# Amplifier.net
KiCad netlist of a schematic drawn in Altium Designer
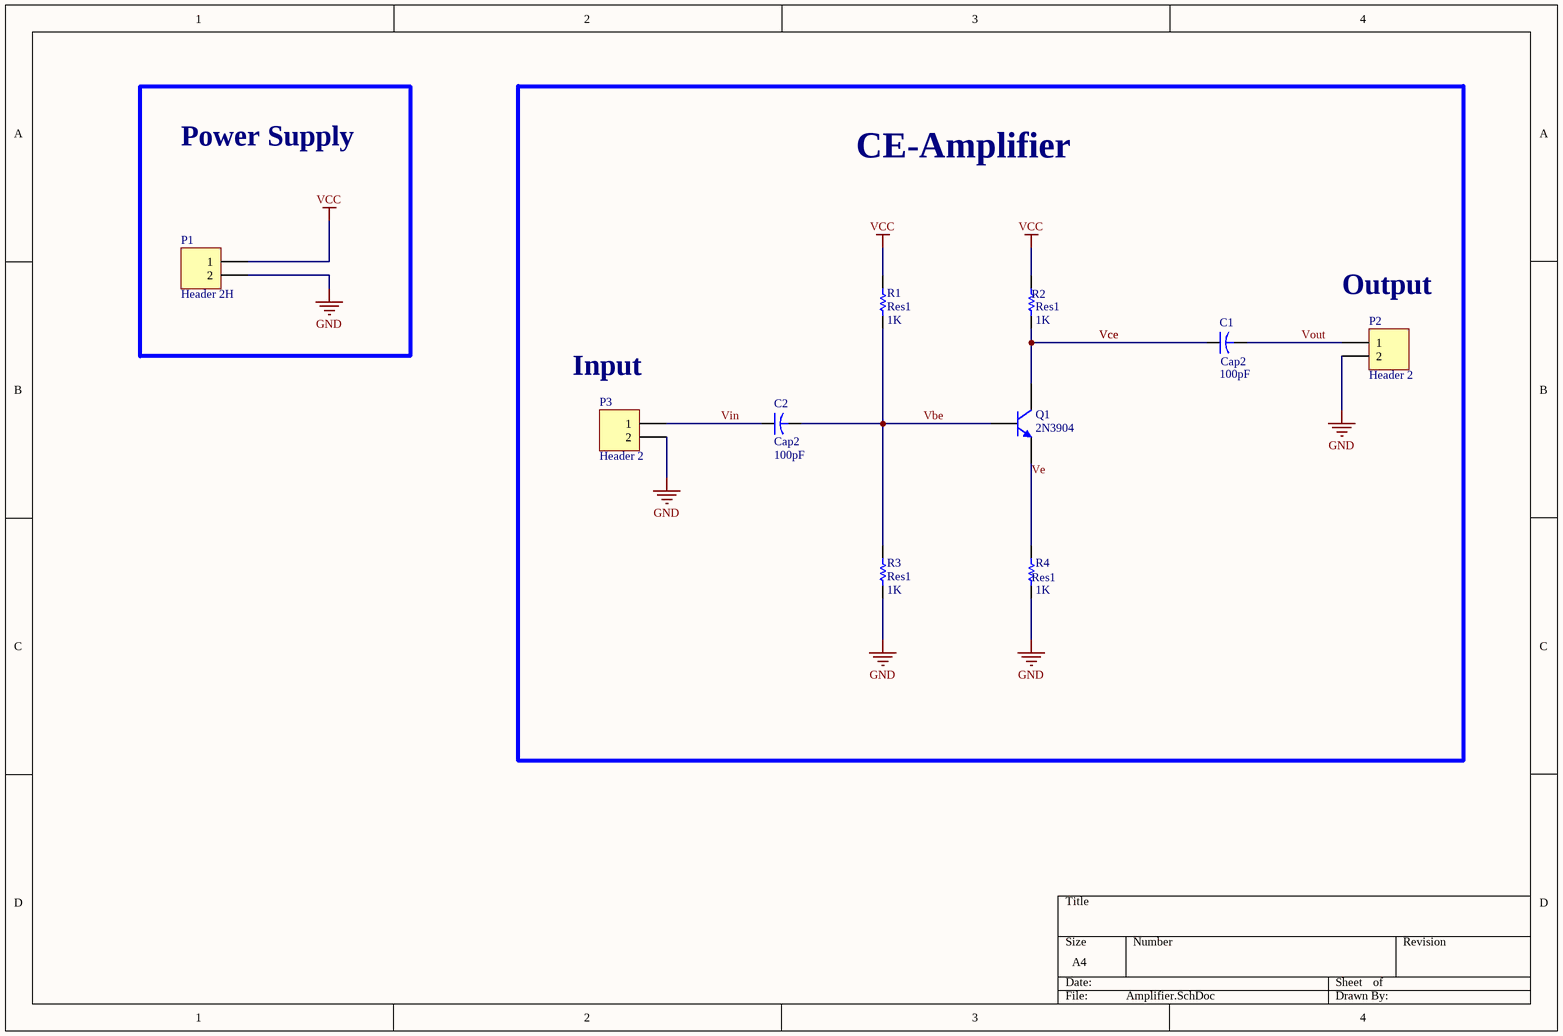
[diagram p0: Amplifier.SchDoc]

(export (version "E")
  (design (tool "Eeschema 10.0.6"))
  (components
    (comp (ref "C1")
      (value "Cap2")
      (footprint "CAPR5-4X5")
      (description "Capacitor")
      (fields (field (name "ALTIUM_VALUE") "100pF") (field (name "PUBLISHER") "Altium Limited"))
      (libsource (lib "Miscellaneous Devices") (part "Cap2"))
    )
    (comp (ref "C2")
      (value "Cap2")
      (footprint "CAPR5-4X5")
      (description "Capacitor")
      (fields (field (name "ALTIUM_VALUE") "100pF") (field (name "PUBLISHER") "Altium Limited"))
      (libsource (lib "Miscellaneous Devices") (part "Cap2"))
    )
    (comp (ref "P1")
      (value "Header 2H")
      (footprint "HDR1X2H")
      (description "Header, 2-Pin, Right Angle")
      (fields (field (name "PUBLISHER") "Altium Limited"))
      (libsource (lib "Miscellaneous Connectors") (part "Header 2H"))
    )
    (comp (ref "P2")
      (value "Header 2")
      (footprint "HDR1X2")
      (description "Header, 2-Pin")
      (fields (field (name "PUBLISHER") "Altium Limited"))
      (libsource (lib "Miscellaneous Connectors") (part "Header 2"))
    )
    (comp (ref "P3")
      (value "Header 2")
      (footprint "HDR1X2")
      (description "Header, 2-Pin")
      (fields (field (name "PUBLISHER") "Altium Limited"))
      (libsource (lib "") (part "Header 2_1"))
    )
    (comp (ref "Q1")
      (value "2N3904")
      (footprint "TO-92A")
      (description "NPN General Purpose Amplifier")
      (fields (field (name "PUBLISHER") "Altium Limited"))
      (libsource (lib "Miscellaneous Devices") (part "2N3904"))
    )
    (comp (ref "R1")
      (value "Res1")
      (footprint "AXIAL-0.3")
      (description "Resistor")
      (fields (field (name "ALTIUM_VALUE") "1K") (field (name "PUBLISHER") "Altium Limited"))
      (libsource (lib "Miscellaneous Devices") (part "Res1"))
    )
    (comp (ref "R2")
      (value "Res1")
      (footprint "AXIAL-0.3")
      (description "Resistor")
      (fields (field (name "ALTIUM_VALUE") "1K") (field (name "PUBLISHER") "Altium Limited"))
      (libsource (lib "Miscellaneous Devices") (part "Res1"))
    )
    (comp (ref "R3")
      (value "Res1")
      (footprint "AXIAL-0.3")
      (description "Resistor")
      (fields (field (name "ALTIUM_VALUE") "1K") (field (name "PUBLISHER") "Altium Limited"))
      (libsource (lib "Miscellaneous Devices") (part "Res1"))
    )
    (comp (ref "R4")
      (value "Res1")
      (footprint "AXIAL-0.3")
      (description "Resistor")
      (fields (field (name "ALTIUM_VALUE") "1K") (field (name "PUBLISHER") "Altium Limited"))
      (libsource (lib "Miscellaneous Devices") (part "Res1"))
    )
  )
  (nets
    (net (code "1") (name "/Vbe") (class "Default")
      (node (ref "C2") (pin "2") (pinfunction "2_2") (pintype "passive"))
      (node (ref "Q1") (pin "2") (pinfunction "B_2") (pintype "passive"))
      (node (ref "R1") (pin "2") (pinfunction "2_2") (pintype "passive"))
      (node (ref "R3") (pin "1") (pinfunction "1_1") (pintype "passive"))
    )
    (net (code "2") (name "/Vce") (class "Default")
      (node (ref "C1") (pin "1") (pinfunction "1_1") (pintype "passive"))
      (node (ref "Q1") (pin "3") (pinfunction "C_3") (pintype "passive"))
      (node (ref "R2") (pin "1") (pinfunction "1_1") (pintype "passive"))
    )
    (net (code "3") (name "/Ve") (class "Default")
      (node (ref "Q1") (pin "1") (pinfunction "E_1") (pintype "passive"))
      (node (ref "R4") (pin "1") (pinfunction "1_1") (pintype "passive"))
    )
    (net (code "4") (name "/Vin") (class "Default")
      (node (ref "C2") (pin "1") (pinfunction "1_1") (pintype "passive"))
      (node (ref "P3") (pin "1") (pinfunction "1_1") (pintype "passive"))
    )
    (net (code "5") (name "/Vout") (class "Default")
      (node (ref "C1") (pin "2") (pinfunction "2_2") (pintype "passive"))
      (node (ref "P2") (pin "1") (pinfunction "1_1") (pintype "passive"))
    )
    (net (code "6") (name "GND") (class "Default")
      (node (ref "P1") (pin "2") (pinfunction "2_2") (pintype "passive"))
      (node (ref "P2") (pin "2") (pinfunction "2_2") (pintype "passive"))
      (node (ref "P3") (pin "2") (pinfunction "2_2") (pintype "passive"))
      (node (ref "R3") (pin "2") (pinfunction "2_2") (pintype "passive"))
      (node (ref "R4") (pin "2") (pinfunction "2_2") (pintype "passive"))
    )
    (net (code "7") (name "VCC") (class "Default")
      (node (ref "P1") (pin "1") (pinfunction "1_1") (pintype "passive"))
      (node (ref "R1") (pin "1") (pinfunction "1_1") (pintype "passive"))
      (node (ref "R2") (pin "2") (pinfunction "2_2") (pintype "passive"))
    )
  )
)
